# output_drivers.net
KiCad netlist of a schematic drawn in Altium Designer
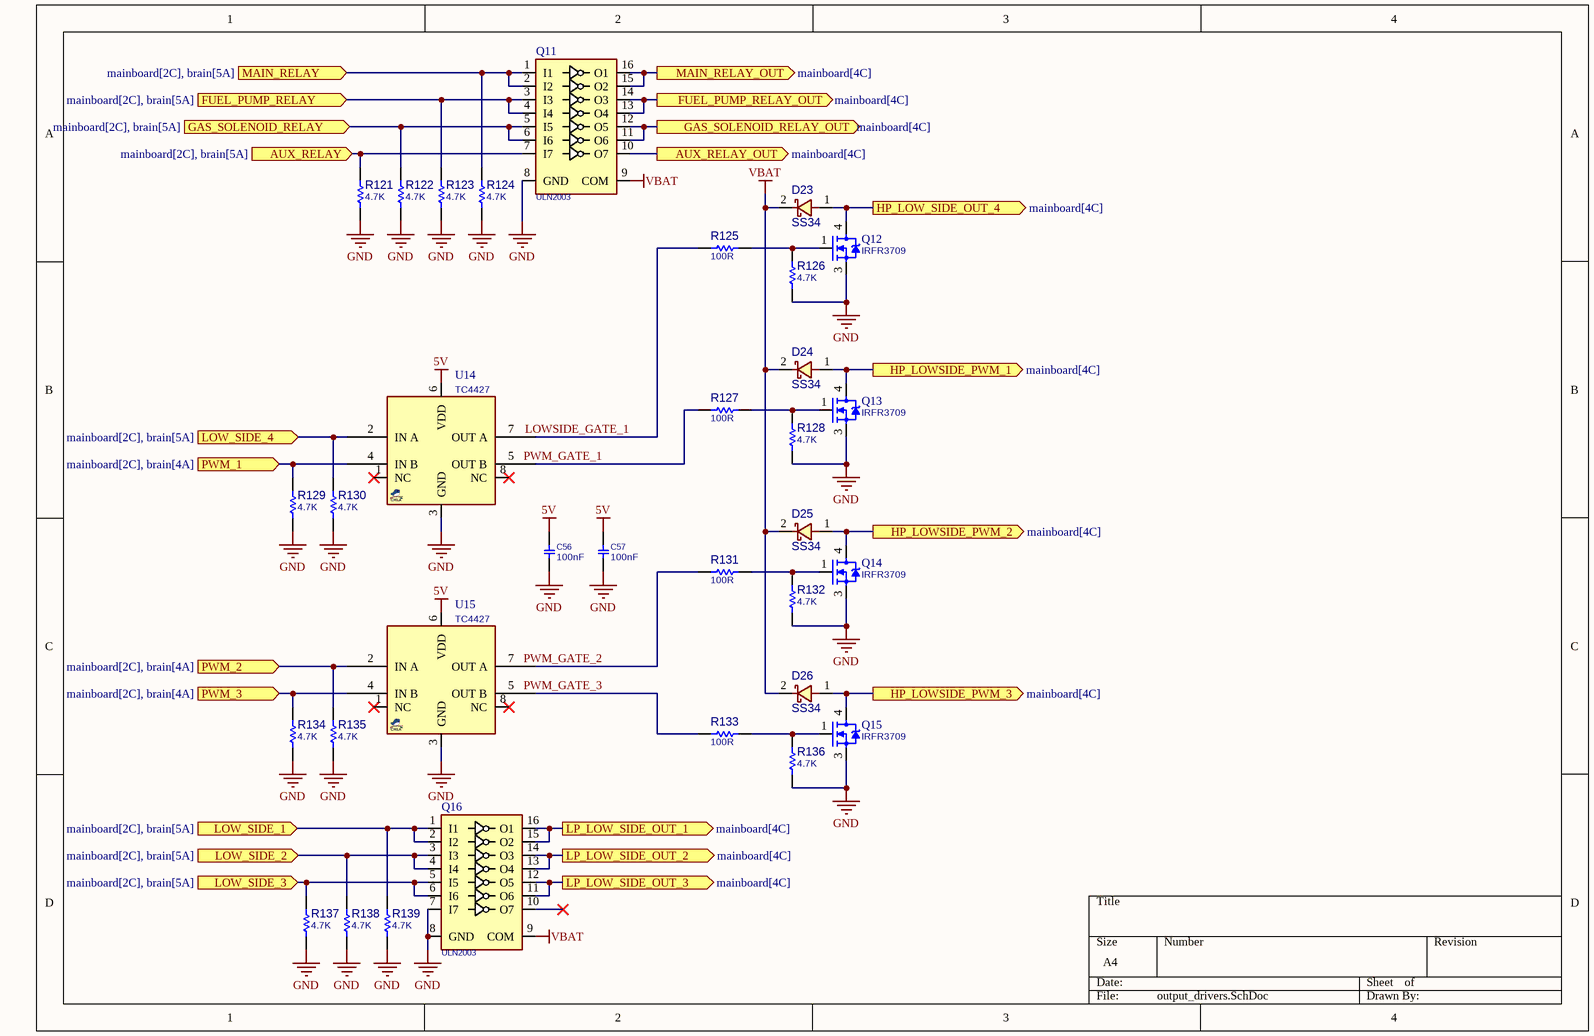
[diagram p0: output_drivers.SchDoc]

(export (version "E")
  (design (tool "Eeschema 10.0.6"))
  (components
    (comp (ref "C56")
      (value "100nF")
      (footprint "C1206")
      (description "CAP, MLCC")
      (fields (field (name "MANF_P#") "MANF_PART#") (field (name "MANF") "Murata"))
      (libsource (lib "passive_smd") (part "CAP_SMD_MLCC"))
    )
    (comp (ref "C57")
      (value "100nF")
      (footprint "C1206")
      (description "CAP, MLCC")
      (fields (field (name "MANF_P#") "MANF_PART#") (field (name "MANF") "Murata"))
      (libsource (lib "passive_smd") (part "CAP_SMD_MLCC"))
    )
    (comp (ref "D23")
      (value "SS34")
      (footprint "D_SMB")
      (description "DIODE, SCHOTTKY, 20V, 3A")
      (fields (field (name "MANF") "VISHAY"))
      (libsource (lib "diode") (part "DIODE_SMD_SCHOTTKY_SS34"))
    )
    (comp (ref "D24")
      (value "SS34")
      (footprint "D_SMB")
      (description "DIODE, SCHOTTKY, 20V, 3A")
      (fields (field (name "MANF") "VISHAY"))
      (libsource (lib "diode") (part "DIODE_SMD_SCHOTTKY_SS34"))
    )
    (comp (ref "D25")
      (value "SS34")
      (footprint "D_SMB")
      (description "DIODE, SCHOTTKY, 20V, 3A")
      (fields (field (name "MANF") "VISHAY"))
      (libsource (lib "diode") (part "DIODE_SMD_SCHOTTKY_SS34"))
    )
    (comp (ref "D26")
      (value "SS34")
      (footprint "D_SMB")
      (description "DIODE, SCHOTTKY, 20V, 3A")
      (fields (field (name "MANF") "VISHAY"))
      (libsource (lib "diode") (part "DIODE_SMD_SCHOTTKY_SS34"))
    )
    (comp (ref "Q11")
      (value "ULN2003")
      (footprint "SO_16_W")
      (description "Darlington, 7-CH, 50V, 0.5A")
      (fields (field (name "MANF_P#") "ULN2003A") (field (name "MANF") "DIODES"))
      (libsource (lib "transistor_bjt") (part "ULN2003_SOP16"))
    )
    (comp (ref "Q12")
      (value "IRFR3709")
      (footprint "DPAK_3")
      (description "MOSFET, N-CH, 30V, 86A, 6.5mRDS, 2300pF")
      (fields (field (name "MANF_P#") "IRFR3709Z"))
      (libsource (lib "transistor_fet") (part "MOSN_IRFR3709_DPAK"))
    )
    (comp (ref "Q13")
      (value "IRFR3709")
      (footprint "DPAK_3")
      (description "MOSFET, N-CH, 30V, 86A, 6.5mRDS, 2300pF")
      (fields (field (name "MANF_P#") "IRFR3709Z"))
      (libsource (lib "transistor_fet") (part "MOSN_IRFR3709_DPAK"))
    )
    (comp (ref "Q14")
      (value "IRFR3709")
      (footprint "DPAK_3")
      (description "MOSFET, N-CH, 30V, 86A, 6.5mRDS, 2300pF")
      (fields (field (name "MANF_P#") "IRFR3709Z"))
      (libsource (lib "transistor_fet") (part "MOSN_IRFR3709_DPAK"))
    )
    (comp (ref "Q15")
      (value "IRFR3709")
      (footprint "DPAK_3")
      (description "MOSFET, N-CH, 30V, 86A, 6.5mRDS, 2300pF")
      (fields (field (name "MANF_P#") "IRFR3709Z"))
      (libsource (lib "transistor_fet") (part "MOSN_IRFR3709_DPAK"))
    )
    (comp (ref "Q16")
      (value "ULN2003")
      (footprint "SO_16_W")
      (description "Darlington, 7-CH, 50V, 0.5A")
      (fields (field (name "MANF_P#") "ULN2003A") (field (name "MANF") "DIODES"))
      (libsource (lib "transistor_bjt") (part "ULN2003_SOP16"))
    )
    (comp (ref "R121")
      (value "4.7K")
      (footprint "R0805")
      (description "RESISTOR, SMD")
      (libsource (lib "passive_smd") (part "RES_SMD_0805"))
    )
    (comp (ref "R122")
      (value "4.7K")
      (footprint "R0805")
      (description "RESISTOR, SMD")
      (libsource (lib "passive_smd") (part "RES_SMD_0805"))
    )
    (comp (ref "R123")
      (value "4.7K")
      (footprint "R0805")
      (description "RESISTOR, SMD")
      (libsource (lib "passive_smd") (part "RES_SMD_0805"))
    )
    (comp (ref "R124")
      (value "4.7K")
      (footprint "R0805")
      (description "RESISTOR, SMD")
      (libsource (lib "passive_smd") (part "RES_SMD_0805"))
    )
    (comp (ref "R125")
      (value "100R")
      (footprint "R1206")
      (description "RESISTOR, SMD")
      (libsource (lib "passive_smd") (part "RES_SMD_1206"))
    )
    (comp (ref "R126")
      (value "4.7K")
      (footprint "R0805")
      (description "RESISTOR, SMD")
      (libsource (lib "passive_smd") (part "RES_SMD_0805"))
    )
    (comp (ref "R127")
      (value "100R")
      (footprint "R1206")
      (description "RESISTOR, SMD")
      (libsource (lib "passive_smd") (part "RES_SMD_1206"))
    )
    (comp (ref "R128")
      (value "4.7K")
      (footprint "R0805")
      (description "RESISTOR, SMD")
      (libsource (lib "passive_smd") (part "RES_SMD_0805"))
    )
    (comp (ref "R129")
      (value "4.7K")
      (footprint "R0805")
      (description "RESISTOR, SMD")
      (libsource (lib "passive_smd") (part "RES_SMD_0805"))
    )
    (comp (ref "R130")
      (value "4.7K")
      (footprint "R0805")
      (description "RESISTOR, SMD")
      (libsource (lib "passive_smd") (part "RES_SMD_0805"))
    )
    (comp (ref "R131")
      (value "100R")
      (footprint "R1206")
      (description "RESISTOR, SMD")
      (libsource (lib "passive_smd") (part "RES_SMD_1206"))
    )
    (comp (ref "R132")
      (value "4.7K")
      (footprint "R0805")
      (description "RESISTOR, SMD")
      (libsource (lib "passive_smd") (part "RES_SMD_0805"))
    )
    (comp (ref "R133")
      (value "100R")
      (footprint "R1206")
      (description "RESISTOR, SMD")
      (libsource (lib "passive_smd") (part "RES_SMD_1206"))
    )
    (comp (ref "R134")
      (value "4.7K")
      (footprint "R0805")
      (description "RESISTOR, SMD")
      (libsource (lib "passive_smd") (part "RES_SMD_0805"))
    )
    (comp (ref "R135")
      (value "4.7K")
      (footprint "R0805")
      (description "RESISTOR, SMD")
      (libsource (lib "passive_smd") (part "RES_SMD_0805"))
    )
    (comp (ref "R136")
      (value "4.7K")
      (footprint "R0805")
      (description "RESISTOR, SMD")
      (libsource (lib "passive_smd") (part "RES_SMD_0805"))
    )
    (comp (ref "R137")
      (value "4.7K")
      (footprint "R0805")
      (description "RESISTOR, SMD")
      (libsource (lib "passive_smd") (part "RES_SMD_0805"))
    )
    (comp (ref "R138")
      (value "4.7K")
      (footprint "R0805")
      (description "RESISTOR, SMD")
      (libsource (lib "passive_smd") (part "RES_SMD_0805"))
    )
    (comp (ref "R139")
      (value "4.7K")
      (footprint "R0805")
      (description "RESISTOR, SMD")
      (libsource (lib "passive_smd") (part "RES_SMD_0805"))
    )
    (comp (ref "U14")
      (value "TC4427")
      (footprint "SO_8")
      (description "power Mosfet Driver, Dual, High-Speed, 1.5A")
      (libsource (lib "transistor_fet") (part "MOS_DUAL_TC4427"))
    )
    (comp (ref "U15")
      (value "TC4427")
      (footprint "SO_8")
      (description "power Mosfet Driver, Dual, High-Speed, 1.5A")
      (libsource (lib "transistor_fet") (part "MOS_DUAL_TC4427"))
    )
  )
  (nets
    (net (code "1") (name "/AUX_RELAY") (class "Default")
      (node (ref "Q11") (pin "7") (pinfunction "I7_7") (pintype "passive"))
      (node (ref "R121") (pin "2") (pinfunction "2_2") (pintype "passive"))
    )
    (net (code "2") (name "/AUX_RELAY_OUT") (class "Default")
      (node (ref "Q11") (pin "10") (pinfunction "O7_10") (pintype "passive"))
    )
    (net (code "3") (name "/FUEL_PUMP_RELAY") (class "Default")
      (node (ref "Q11") (pin "3") (pinfunction "I3_3") (pintype "passive"))
      (node (ref "Q11") (pin "4") (pinfunction "I4_4") (pintype "passive"))
      (node (ref "R123") (pin "2") (pinfunction "2_2") (pintype "passive"))
    )
    (net (code "4") (name "/FUEL_PUMP_RELAY_OUT") (class "Default")
      (node (ref "Q11") (pin "13") (pinfunction "O4_13") (pintype "passive"))
      (node (ref "Q11") (pin "14") (pinfunction "O3_14") (pintype "passive"))
    )
    (net (code "5") (name "/GAS_SOLENOID_RELAY") (class "Default")
      (node (ref "Q11") (pin "5") (pinfunction "I5_5") (pintype "passive"))
      (node (ref "Q11") (pin "6") (pinfunction "I6_6") (pintype "passive"))
      (node (ref "R122") (pin "2") (pinfunction "2_2") (pintype "passive"))
    )
    (net (code "6") (name "/GAS_SOLENOID_RELAY_OUT") (class "Default")
      (node (ref "Q11") (pin "11") (pinfunction "O6_11") (pintype "passive"))
      (node (ref "Q11") (pin "12") (pinfunction "O5_12") (pintype "passive"))
    )
    (net (code "7") (name "/HP_LOWSIDE_PWM_1") (class "Default")
      (node (ref "D24") (pin "1") (pinfunction "1_1") (pintype "passive"))
      (node (ref "Q13") (pin "4") (pinfunction "D_4") (pintype "passive"))
    )
    (net (code "8") (name "/HP_LOWSIDE_PWM_2") (class "Default")
      (node (ref "D25") (pin "1") (pinfunction "1_1") (pintype "passive"))
      (node (ref "Q14") (pin "4") (pinfunction "D_4") (pintype "passive"))
    )
    (net (code "9") (name "/HP_LOWSIDE_PWM_3") (class "Default")
      (node (ref "D26") (pin "1") (pinfunction "1_1") (pintype "passive"))
      (node (ref "Q15") (pin "4") (pinfunction "D_4") (pintype "passive"))
    )
    (net (code "10") (name "/HP_LOW_SIDE_OUT_4") (class "Default")
      (node (ref "D23") (pin "1") (pinfunction "1_1") (pintype "passive"))
      (node (ref "Q12") (pin "4") (pinfunction "D_4") (pintype "passive"))
    )
    (net (code "11") (name "/LOWSIDE_GATE_1") (class "Default")
      (node (ref "R125") (pin "1") (pinfunction "1_1") (pintype "passive"))
      (node (ref "U14") (pin "7") (pinfunction "OUT_A_7") (pintype "passive"))
    )
    (net (code "12") (name "/LOW_SIDE_1") (class "Default")
      (node (ref "Q16") (pin "1") (pinfunction "I1_1") (pintype "passive"))
      (node (ref "Q16") (pin "2") (pinfunction "I2_2") (pintype "passive"))
      (node (ref "R139") (pin "2") (pinfunction "2_2") (pintype "passive"))
    )
    (net (code "13") (name "/LOW_SIDE_2") (class "Default")
      (node (ref "Q16") (pin "3") (pinfunction "I3_3") (pintype "passive"))
      (node (ref "Q16") (pin "4") (pinfunction "I4_4") (pintype "passive"))
      (node (ref "R138") (pin "2") (pinfunction "2_2") (pintype "passive"))
    )
    (net (code "14") (name "/LOW_SIDE_3") (class "Default")
      (node (ref "Q16") (pin "5") (pinfunction "I5_5") (pintype "passive"))
      (node (ref "Q16") (pin "6") (pinfunction "I6_6") (pintype "passive"))
      (node (ref "R137") (pin "2") (pinfunction "2_2") (pintype "passive"))
    )
    (net (code "15") (name "/LOW_SIDE_4") (class "Default")
      (node (ref "R130") (pin "2") (pinfunction "2_2") (pintype "passive"))
      (node (ref "U14") (pin "2") (pinfunction "IN_A_2") (pintype "passive"))
    )
    (net (code "16") (name "/LP_LOW_SIDE_OUT_1") (class "Default")
      (node (ref "Q16") (pin "15") (pinfunction "O2_15") (pintype "passive"))
      (node (ref "Q16") (pin "16") (pinfunction "O1_16") (pintype "passive"))
    )
    (net (code "17") (name "/LP_LOW_SIDE_OUT_2") (class "Default")
      (node (ref "Q16") (pin "13") (pinfunction "O4_13") (pintype "passive"))
      (node (ref "Q16") (pin "14") (pinfunction "O3_14") (pintype "passive"))
    )
    (net (code "18") (name "/LP_LOW_SIDE_OUT_3") (class "Default")
      (node (ref "Q16") (pin "11") (pinfunction "O6_11") (pintype "passive"))
      (node (ref "Q16") (pin "12") (pinfunction "O5_12") (pintype "passive"))
    )
    (net (code "19") (name "/MAIN_RELAY") (class "Default")
      (node (ref "Q11") (pin "1") (pinfunction "I1_1") (pintype "passive"))
      (node (ref "Q11") (pin "2") (pinfunction "I2_2") (pintype "passive"))
      (node (ref "R124") (pin "2") (pinfunction "2_2") (pintype "passive"))
    )
    (net (code "20") (name "/MAIN_RELAY_OUT") (class "Default")
      (node (ref "Q11") (pin "15") (pinfunction "O2_15") (pintype "passive"))
      (node (ref "Q11") (pin "16") (pinfunction "O1_16") (pintype "passive"))
    )
    (net (code "21") (name "/PWM_1") (class "Default")
      (node (ref "R129") (pin "2") (pinfunction "2_2") (pintype "passive"))
      (node (ref "U14") (pin "4") (pinfunction "IN_B_4") (pintype "passive"))
    )
    (net (code "22") (name "/PWM_2") (class "Default")
      (node (ref "R135") (pin "2") (pinfunction "2_2") (pintype "passive"))
      (node (ref "U15") (pin "2") (pinfunction "IN_A_2") (pintype "passive"))
    )
    (net (code "23") (name "/PWM_3") (class "Default")
      (node (ref "R134") (pin "2") (pinfunction "2_2") (pintype "passive"))
      (node (ref "U15") (pin "4") (pinfunction "IN_B_4") (pintype "passive"))
    )
    (net (code "24") (name "/PWM_GATE_1") (class "Default")
      (node (ref "R127") (pin "2") (pinfunction "2_2") (pintype "passive"))
      (node (ref "U14") (pin "5") (pinfunction "OUT_B_5") (pintype "passive"))
    )
    (net (code "25") (name "/PWM_GATE_2") (class "Default")
      (node (ref "R131") (pin "2") (pinfunction "2_2") (pintype "passive"))
      (node (ref "U15") (pin "7") (pinfunction "OUT_A_7") (pintype "passive"))
    )
    (net (code "26") (name "/PWM_GATE_3") (class "Default")
      (node (ref "R133") (pin "2") (pinfunction "2_2") (pintype "passive"))
      (node (ref "U15") (pin "5") (pinfunction "OUT_B_5") (pintype "passive"))
    )
    (net (code "27") (name "5V") (class "Default")
      (node (ref "C56") (pin "2") (pinfunction "2_2") (pintype "passive"))
      (node (ref "C57") (pin "2") (pinfunction "2_2") (pintype "passive"))
      (node (ref "U14") (pin "6") (pinfunction "VDD_6") (pintype "passive"))
      (node (ref "U15") (pin "6") (pinfunction "VDD_6") (pintype "passive"))
    )
    (net (code "28") (name "GND") (class "Default")
      (node (ref "C56") (pin "1") (pinfunction "1_1") (pintype "passive"))
      (node (ref "C57") (pin "1") (pinfunction "1_1") (pintype "passive"))
      (node (ref "Q11") (pin "8") (pinfunction "GND_8") (pintype "passive"))
      (node (ref "Q12") (pin "3") (pinfunction "S_3") (pintype "passive"))
      (node (ref "Q13") (pin "3") (pinfunction "S_3") (pintype "passive"))
      (node (ref "Q14") (pin "3") (pinfunction "S_3") (pintype "passive"))
      (node (ref "Q15") (pin "3") (pinfunction "S_3") (pintype "passive"))
      (node (ref "Q16") (pin "7") (pinfunction "I7_7") (pintype "passive"))
      (node (ref "Q16") (pin "8") (pinfunction "GND_8") (pintype "passive"))
      (node (ref "R121") (pin "1") (pinfunction "1_1") (pintype "passive"))
      (node (ref "R122") (pin "1") (pinfunction "1_1") (pintype "passive"))
      (node (ref "R123") (pin "1") (pinfunction "1_1") (pintype "passive"))
      (node (ref "R124") (pin "1") (pinfunction "1_1") (pintype "passive"))
      (node (ref "R126") (pin "1") (pinfunction "1_1") (pintype "passive"))
      (node (ref "R128") (pin "1") (pinfunction "1_1") (pintype "passive"))
      (node (ref "R129") (pin "1") (pinfunction "1_1") (pintype "passive"))
      (node (ref "R130") (pin "1") (pinfunction "1_1") (pintype "passive"))
      (node (ref "R132") (pin "1") (pinfunction "1_1") (pintype "passive"))
      (node (ref "R134") (pin "1") (pinfunction "1_1") (pintype "passive"))
      (node (ref "R135") (pin "1") (pinfunction "1_1") (pintype "passive"))
      (node (ref "R136") (pin "1") (pinfunction "1_1") (pintype "passive"))
      (node (ref "R137") (pin "1") (pinfunction "1_1") (pintype "passive"))
      (node (ref "R138") (pin "1") (pinfunction "1_1") (pintype "passive"))
      (node (ref "R139") (pin "1") (pinfunction "1_1") (pintype "passive"))
      (node (ref "U14") (pin "3") (pinfunction "GND_3") (pintype "passive"))
      (node (ref "U15") (pin "3") (pinfunction "GND_3") (pintype "passive"))
    )
    (net (code "29") (name "Net-(Q12-G)") (class "Default")
      (node (ref "Q12") (pin "1") (pinfunction "G_1") (pintype "passive"))
      (node (ref "R125") (pin "2") (pinfunction "2_2") (pintype "passive"))
      (node (ref "R126") (pin "2") (pinfunction "2_2") (pintype "passive"))
    )
    (net (code "30") (name "Net-(Q13-G)") (class "Default")
      (node (ref "Q13") (pin "1") (pinfunction "G_1") (pintype "passive"))
      (node (ref "R127") (pin "1") (pinfunction "1_1") (pintype "passive"))
      (node (ref "R128") (pin "2") (pinfunction "2_2") (pintype "passive"))
    )
    (net (code "31") (name "Net-(Q14-G)") (class "Default")
      (node (ref "Q14") (pin "1") (pinfunction "G_1") (pintype "passive"))
      (node (ref "R131") (pin "1") (pinfunction "1_1") (pintype "passive"))
      (node (ref "R132") (pin "2") (pinfunction "2_2") (pintype "passive"))
    )
    (net (code "32") (name "Net-(Q15-G)") (class "Default")
      (node (ref "Q15") (pin "1") (pinfunction "G_1") (pintype "passive"))
      (node (ref "R133") (pin "1") (pinfunction "1_1") (pintype "passive"))
      (node (ref "R136") (pin "2") (pinfunction "2_2") (pintype "passive"))
    )
    (net (code "33") (name "VBAT") (class "Default")
      (node (ref "D23") (pin "2") (pinfunction "2_2") (pintype "passive"))
      (node (ref "D24") (pin "2") (pinfunction "2_2") (pintype "passive"))
      (node (ref "D25") (pin "2") (pinfunction "2_2") (pintype "passive"))
      (node (ref "D26") (pin "2") (pinfunction "2_2") (pintype "passive"))
      (node (ref "Q11") (pin "9") (pinfunction "COM_9") (pintype "passive"))
      (node (ref "Q16") (pin "9") (pinfunction "COM_9") (pintype "passive"))
    )
    (net (code "34") (name "unconnected-(Q16-O7-Pad10)") (class "Default")
      (node (ref "Q16") (pin "10") (pinfunction "O7_10") (pintype "passive+no_connect"))
    )
    (net (code "35") (name "unconnected-(U14-NC-Pad1)") (class "Default")
      (node (ref "U14") (pin "1") (pinfunction "NC_1") (pintype "passive+no_connect"))
    )
    (net (code "36") (name "unconnected-(U14-NC-Pad8)") (class "Default")
      (node (ref "U14") (pin "8") (pinfunction "NC_8") (pintype "passive+no_connect"))
    )
    (net (code "37") (name "unconnected-(U15-NC-Pad1)") (class "Default")
      (node (ref "U15") (pin "1") (pinfunction "NC_1") (pintype "passive+no_connect"))
    )
    (net (code "38") (name "unconnected-(U15-NC-Pad8)") (class "Default")
      (node (ref "U15") (pin "8") (pinfunction "NC_8") (pintype "passive+no_connect"))
    )
  )
)
